# SCH_Argon_flow_controller_2021-09-11.net
KiCad netlist of a schematic drawn in EasyEDA
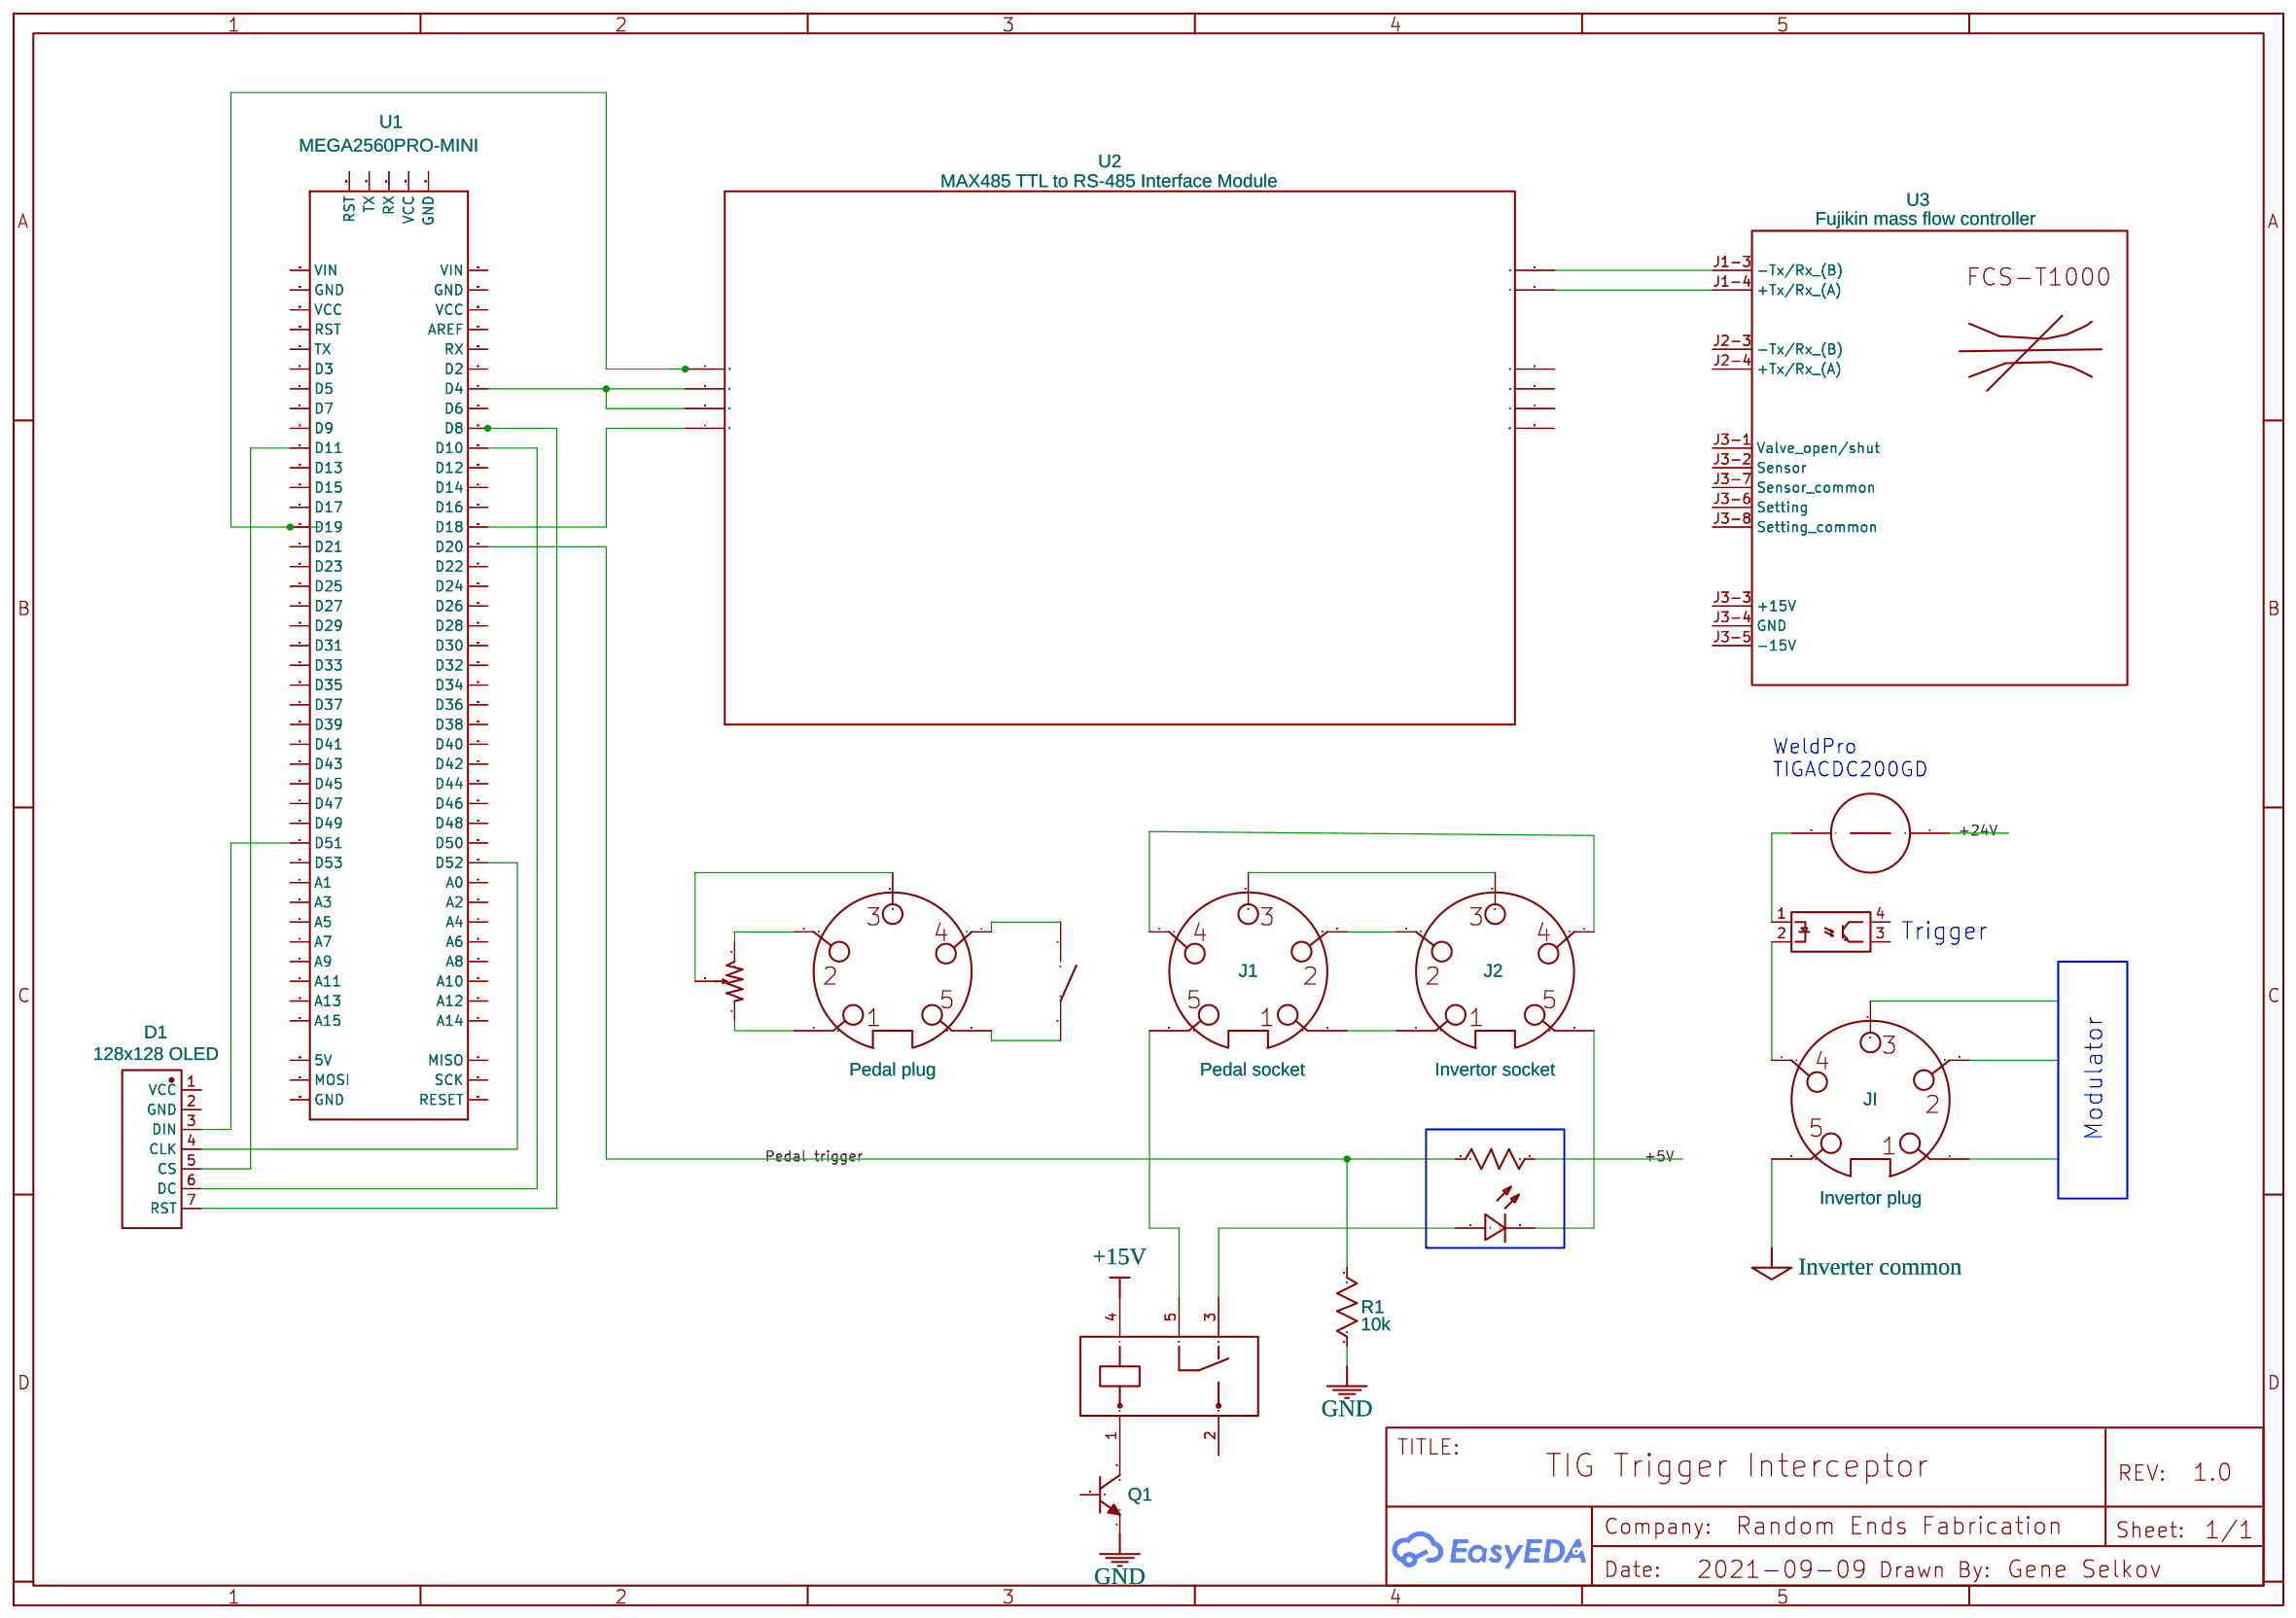
[diagram p0: schematic sheet]

(export (version "E")
  (design (tool "Eeschema 10.0.6"))
  (components
    (comp (ref "CS") (value "Current source") (libsource (lib "") (part "Current source")))
    (comp (ref "D1") (value "128x128 OLED") (libsource (lib "") (part "128x128 OLED")))
    (comp (ref "IC1")
      (value "Trigger")
      (libsource (lib "") (part "Optocoupler_SMD_KPC357_LTV35x_PC357_SingleChannel"))
    )
    (comp (ref "J0")
      (value "Pedal plug")
      (fields
        (field (name "BOM_Manufacturer Part") "Unknown")
        (field (name "BOM_Supplier Part") "CON-HK1705")
      )
      (libsource (lib "") (part "Weipu 5 connector_1"))
    )
    (comp (ref "J1")
      (value "Pedal socket")
      (fields
        (field (name "BOM_Manufacturer Part") "Unknown")
        (field (name "BOM_Supplier Part") "CON-HK1705")
      )
      (libsource (lib "") (part "Weipu 5 connector_3"))
    )
    (comp (ref "J2")
      (value "Invertor socket")
      (fields
        (field (name "BOM_Manufacturer Part") "Unknown")
        (field (name "BOM_Supplier Part") "CON-HK1705")
      )
      (libsource (lib "") (part "Weipu 5 connector_2"))
    )
    (comp (ref "JI")
      (value "Invertor plug")
      (fields
        (field (name "BOM_Manufacturer Part") "Unknown")
        (field (name "BOM_Supplier Part") "CON-HK1705")
      )
      (libsource (lib "") (part "Weipu 5 connector"))
    )
    (comp (ref "LED1")
      (value "LED-Red(0805)")
      (fields
        (field (name "BOM_Manufacturer Part") "17-21SURC/S530-A2/TR8")
        (field (name "BOM_Supplier Part") "C131244")
      )
      (libsource (lib "") (part "LED-Red(0805)"))
    )
    (comp (ref "PHR") (value "1 .. 40k") (libsource (lib "") (part "R_0603_US_1")))
    (comp (ref "POT") (value "POTENTIOMETER") (libsource (lib "") (part "POTENTIOMETER")))
    (comp (ref "Q1")
      (value "MPSA06-AT/P")
      (fields (field (name "BOM_Supplier Part") "C112894"))
      (libsource (lib "") (part "MPSA06-AT/P"))
    )
    (comp (ref "R1") (value "10k") (libsource (lib "") (part "R_0603_US")))
    (comp (ref "RELAY1")
      (value "SRD-12VDC-SL-C")
      (fields (field (name "BOM_Supplier Part") "C30431"))
      (libsource (lib "") (part "SRD-12VDC-SL-C"))
    )
    (comp (ref "S1") (value "Switch") (libsource (lib "") (part "Switch")))
    (comp (ref "U1") (value "MEGA2560PRO-MINI") (libsource (lib "") (part "MEGA2560PRO-MINI")))
    (comp (ref "U2")
      (value "MAX485 TTL to RS-485 Interface Module")
      (libsource (lib "") (part "MAX485 TTL to RS-485 Interface Module"))
    )
    (comp (ref "U3")
      (value "Fujikin mass flow controller")
      (fields (field (name "BOM_Manufacturer Part") "FCS-T1000"))
      (libsource (lib "") (part "Fujikin mass flow controller"))
    )
  )
  (nets
    (net (code "1") (name "+15V") (class "Default")
      (node (ref "RELAY1") (pin "4") (pinfunction "4_4") (pintype "input"))
    )
    (net (code "2") (name "/+5V") (class "Default")
      (node (ref "PHR") (pin "2") (pinfunction "2_2") (pintype "unspecified"))
    )
    (net (code "3") (name "/+24V") (class "Default")
      (node (ref "CS") (pin "1") (pinfunction "+_1") (pintype "unspecified"))
    )
    (net (code "4") (name "/Pedal trigger") (class "Default")
      (node (ref "PHR") (pin "1") (pinfunction "1_1") (pintype "unspecified"))
      (node (ref "R1") (pin "1") (pinfunction "1_1") (pintype "unspecified"))
      (node (ref "U1") (pin "D20") (pinfunction "D20_D20") (pintype "bidirectional"))
    )
    (net (code "5") (name "GND") (class "Default")
      (node (ref "Q1") (pin "1") (pinfunction "E_1") (pintype "input"))
      (node (ref "R1") (pin "2") (pinfunction "2_2") (pintype "unspecified"))
    )
    (net (code "6") (name "Inverter common") (class "Default")
      (node (ref "JI") (pin "5") (pinfunction "5_5") (pintype "unspecified"))
    )
    (net (code "7") (name "Net-(CS--)") (class "Default")
      (node (ref "CS") (pin "2") (pinfunction "-_2") (pintype "unspecified"))
      (node (ref "IC1") (pin "1") (pintype "unspecified"))
    )
    (net (code "8") (name "Net-(D1-CLK)") (class "Default")
      (node (ref "D1") (pin "4") (pinfunction "CLK_4") (pintype "input"))
      (node (ref "U1") (pin "D52") (pinfunction "D52_D52") (pintype "bidirectional"))
    )
    (net (code "9") (name "Net-(D1-CS)") (class "Default")
      (node (ref "D1") (pin "5") (pinfunction "CS_5") (pintype "input"))
      (node (ref "U1") (pin "D11") (pinfunction "D11_D11") (pintype "bidirectional"))
    )
    (net (code "10") (name "Net-(D1-DC)") (class "Default")
      (node (ref "D1") (pin "6") (pinfunction "DC_6") (pintype "unspecified"))
      (node (ref "U1") (pin "D10") (pinfunction "D10_D10") (pintype "bidirectional"))
    )
    (net (code "11") (name "Net-(D1-DIN)") (class "Default")
      (node (ref "D1") (pin "3") (pinfunction "DIN_3") (pintype "unspecified"))
      (node (ref "U1") (pin "D51") (pinfunction "D51_D51") (pintype "bidirectional"))
    )
    (net (code "12") (name "Net-(D1-RST)") (class "Default")
      (node (ref "D1") (pin "7") (pinfunction "RST_7") (pintype "input"))
      (node (ref "U1") (pin "D8") (pinfunction "D8_D8") (pintype "bidirectional"))
    )
    (net (code "13") (name "Net-(IC1-Pad2)") (class "Default")
      (node (ref "IC1") (pin "2") (pintype "unspecified"))
      (node (ref "JI") (pin "4") (pinfunction "4_4") (pintype "unspecified"))
    )
    (net (code "14") (name "Net-(J0-Pad1)") (class "Default")
      (node (ref "J0") (pin "1") (pinfunction "1_1") (pintype "unspecified"))
      (node (ref "POT") (pin "1") (pinfunction "1_1") (pintype "unspecified"))
    )
    (net (code "15") (name "Net-(J0-Pad2)") (class "Default")
      (node (ref "J0") (pin "2") (pinfunction "2_2") (pintype "unspecified"))
      (node (ref "POT") (pin "2") (pinfunction "2_2") (pintype "unspecified"))
    )
    (net (code "16") (name "Net-(J0-Pad3)") (class "Default")
      (node (ref "J0") (pin "3") (pinfunction "3_3") (pintype "unspecified"))
      (node (ref "POT") (pin "3") (pinfunction "3_3") (pintype "unspecified"))
    )
    (net (code "17") (name "Net-(J0-Pad4)") (class "Default")
      (node (ref "J0") (pin "4") (pinfunction "4_4") (pintype "unspecified"))
      (node (ref "S1") (pin "1") (pinfunction "1_1") (pintype "unspecified"))
    )
    (net (code "18") (name "Net-(J0-Pad5)") (class "Default")
      (node (ref "J0") (pin "5") (pinfunction "5_5") (pintype "unspecified"))
      (node (ref "S1") (pin "2") (pinfunction "2_2") (pintype "unspecified"))
    )
    (net (code "19") (name "Net-(J1-Pad1)") (class "Default")
      (node (ref "J1") (pin "1") (pinfunction "1_1") (pintype "unspecified"))
      (node (ref "J2") (pin "1") (pinfunction "1_1") (pintype "unspecified"))
    )
    (net (code "20") (name "Net-(J1-Pad2)") (class "Default")
      (node (ref "J1") (pin "2") (pinfunction "2_2") (pintype "unspecified"))
      (node (ref "J2") (pin "2") (pinfunction "2_2") (pintype "unspecified"))
    )
    (net (code "21") (name "Net-(J1-Pad3)") (class "Default")
      (node (ref "J1") (pin "3") (pinfunction "3_3") (pintype "unspecified"))
      (node (ref "J2") (pin "3") (pinfunction "3_3") (pintype "unspecified"))
    )
    (net (code "22") (name "Net-(J1-Pad4)") (class "Default")
      (node (ref "J1") (pin "4") (pinfunction "4_4") (pintype "unspecified"))
      (node (ref "J2") (pin "4") (pinfunction "4_4") (pintype "unspecified"))
    )
    (net (code "23") (name "Net-(J1-Pad5)") (class "Default")
      (node (ref "J1") (pin "5") (pinfunction "5_5") (pintype "unspecified"))
      (node (ref "RELAY1") (pin "5") (pinfunction "5_5") (pintype "input"))
    )
    (net (code "24") (name "Net-(LED1-+)") (class "Default")
      (node (ref "LED1") (pin "1") (pinfunction "+_1") (pintype "unspecified"))
      (node (ref "RELAY1") (pin "3") (pinfunction "3_3") (pintype "input"))
    )
    (net (code "25") (name "Net-(LED1--)") (class "Default")
      (node (ref "J2") (pin "5") (pinfunction "5_5") (pintype "unspecified"))
      (node (ref "LED1") (pin "2") (pinfunction "-_2") (pintype "unspecified"))
    )
    (net (code "26") (name "Net-(Q1-C)") (class "Default")
      (node (ref "Q1") (pin "3") (pinfunction "C_3") (pintype "input"))
      (node (ref "RELAY1") (pin "1") (pinfunction "1_1") (pintype "input"))
    )
    (net (code "27") (name "Net-(U2-A-Pad10)") (class "Default")
      (node (ref "U2") (pin "10") (pinfunction "A_10") (pintype "bidirectional"))
      (node (ref "U3") (pin "J1-4") (pinfunction "+Tx/Rx_(A)_J1-4") (pintype "bidirectional"))
    )
    (net (code "28") (name "Net-(U2-B-Pad9)") (class "Default")
      (node (ref "U2") (pin "9") (pinfunction "B_9") (pintype "bidirectional"))
      (node (ref "U3") (pin "J1-3") (pinfunction "-Tx/Rx_(B)_J1-3") (pintype "bidirectional"))
    )
    (net (code "29") (name "Net-(U2-DE)") (class "Default")
      (node (ref "U1") (pin "D4") (pinfunction "D4_D4") (pintype "bidirectional"))
      (node (ref "U2") (pin "2") (pinfunction "RE_2") (pintype "input"))
      (node (ref "U2") (pin "3") (pinfunction "DE_3") (pintype "input"))
    )
    (net (code "30") (name "Net-(U2-DI)") (class "Default")
      (node (ref "U1") (pin "D18") (pinfunction "D18_D18") (pintype "bidirectional"))
      (node (ref "U2") (pin "4") (pinfunction "DI_4") (pintype "input"))
    )
    (net (code "31") (name "Net-(U2-RO)") (class "Default")
      (node (ref "U1") (pin "D19") (pinfunction "D19_D19") (pintype "bidirectional"))
      (node (ref "U2") (pin "1") (pinfunction "RO_1") (pintype "output"))
    )
    (net (code "32") (name "unconnected-(D1-GND-Pad2)") (class "Default")
      (node (ref "D1") (pin "2") (pinfunction "GND_2") (pintype "passive"))
    )
    (net (code "33") (name "unconnected-(D1-VCC-Pad1)") (class "Default")
      (node (ref "D1") (pin "1") (pinfunction "VCC_1") (pintype "passive"))
    )
    (net (code "34") (name "unconnected-(IC1-Pad3)") (class "Default")
      (node (ref "IC1") (pin "3") (pintype "unspecified"))
    )
    (net (code "35") (name "unconnected-(IC1-Pad4)") (class "Default")
      (node (ref "IC1") (pin "4") (pintype "unspecified"))
    )
    (net (code "36") (name "unconnected-(JI-Pad1)") (class "Default")
      (node (ref "JI") (pin "1") (pinfunction "1_1") (pintype "unspecified"))
    )
    (net (code "37") (name "unconnected-(JI-Pad2)") (class "Default")
      (node (ref "JI") (pin "2") (pinfunction "2_2") (pintype "unspecified"))
    )
    (net (code "38") (name "unconnected-(JI-Pad3)") (class "Default")
      (node (ref "JI") (pin "3") (pinfunction "3_3") (pintype "unspecified"))
    )
    (net (code "39") (name "unconnected-(Q1-B-Pad2)") (class "Default")
      (node (ref "Q1") (pin "2") (pinfunction "B_2") (pintype "input"))
    )
    (net (code "40") (name "unconnected-(RELAY1-Pad2)") (class "Default")
      (node (ref "RELAY1") (pin "2") (pinfunction "2_2") (pintype "input"))
    )
    (net (code "41") (name "unconnected-(U1-5V-Pad5V@3)") (class "Default")
      (node (ref "U1") (pin "5V@3") (pinfunction "5V_5V@3") (pintype "bidirectional"))
    )
    (net (code "42") (name "unconnected-(U1-GND-PadGND@1)") (class "Default")
      (node (ref "U1") (pin "GND@1") (pinfunction "GND_GND@1") (pintype "bidirectional"))
    )
    (net (code "43") (name "unconnected-(U1-GND-PadGND@2)") (class "Default")
      (node (ref "U1") (pin "GND@2") (pinfunction "GND_GND@2") (pintype "bidirectional"))
    )
    (net (code "44") (name "unconnected-(U1-GND-PadGND@3)") (class "Default")
      (node (ref "U1") (pin "GND@3") (pinfunction "GND_GND@3") (pintype "bidirectional"))
    )
    (net (code "45") (name "unconnected-(U1-GND-PadGND@4)") (class "Default")
      (node (ref "U1") (pin "GND@4") (pinfunction "GND_GND@4") (pintype "bidirectional"))
    )
    (net (code "46") (name "unconnected-(U1-PadA0)") (class "Default")
      (node (ref "U1") (pin "A0") (pinfunction "A0_A0") (pintype "bidirectional"))
    )
    (net (code "47") (name "unconnected-(U1-PadA1)") (class "Default")
      (node (ref "U1") (pin "A1") (pinfunction "A1_A1") (pintype "bidirectional"))
    )
    (net (code "48") (name "unconnected-(U1-PadA2)") (class "Default")
      (node (ref "U1") (pin "A2") (pinfunction "A2_A2") (pintype "bidirectional"))
    )
    (net (code "49") (name "unconnected-(U1-PadA3)") (class "Default")
      (node (ref "U1") (pin "A3") (pinfunction "A3_A3") (pintype "bidirectional"))
    )
    (net (code "50") (name "unconnected-(U1-PadA4)") (class "Default")
      (node (ref "U1") (pin "A4") (pinfunction "A4_A4") (pintype "bidirectional"))
    )
    (net (code "51") (name "unconnected-(U1-PadA5)") (class "Default")
      (node (ref "U1") (pin "A5") (pinfunction "A5_A5") (pintype "bidirectional"))
    )
    (net (code "52") (name "unconnected-(U1-PadA6)") (class "Default")
      (node (ref "U1") (pin "A6") (pinfunction "A6_A6") (pintype "bidirectional"))
    )
    (net (code "53") (name "unconnected-(U1-PadA7)") (class "Default")
      (node (ref "U1") (pin "A7") (pinfunction "A7_A7") (pintype "bidirectional"))
    )
    (net (code "54") (name "unconnected-(U1-PadA8)") (class "Default")
      (node (ref "U1") (pin "A8") (pinfunction "A8_A8") (pintype "bidirectional"))
    )
    (net (code "55") (name "unconnected-(U1-PadA9)") (class "Default")
      (node (ref "U1") (pin "A9") (pinfunction "A9_A9") (pintype "bidirectional"))
    )
    (net (code "56") (name "unconnected-(U1-PadA10)") (class "Default")
      (node (ref "U1") (pin "A10") (pinfunction "A10_A10") (pintype "bidirectional"))
    )
    (net (code "57") (name "unconnected-(U1-PadA11)") (class "Default")
      (node (ref "U1") (pin "A11") (pinfunction "A11_A11") (pintype "bidirectional"))
    )
    (net (code "58") (name "unconnected-(U1-PadA12)") (class "Default")
      (node (ref "U1") (pin "A12") (pinfunction "A12_A12") (pintype "bidirectional"))
    )
    (net (code "59") (name "unconnected-(U1-PadA13)") (class "Default")
      (node (ref "U1") (pin "A13") (pinfunction "A13_A13") (pintype "bidirectional"))
    )
    (net (code "60") (name "unconnected-(U1-PadA14)") (class "Default")
      (node (ref "U1") (pin "A14") (pinfunction "A14_A14") (pintype "bidirectional"))
    )
    (net (code "61") (name "unconnected-(U1-PadA15)") (class "Default")
      (node (ref "U1") (pin "A15") (pinfunction "A15_A15") (pintype "bidirectional"))
    )
    (net (code "62") (name "unconnected-(U1-PadAREF)") (class "Default")
      (node (ref "U1") (pin "AREF") (pinfunction "AREF_AREF") (pintype "bidirectional"))
    )
    (net (code "63") (name "unconnected-(U1-PadD2)") (class "Default")
      (node (ref "U1") (pin "D2") (pinfunction "D2_D2") (pintype "bidirectional"))
    )
    (net (code "64") (name "unconnected-(U1-PadD3)") (class "Default")
      (node (ref "U1") (pin "D3") (pinfunction "D3_D3") (pintype "bidirectional"))
    )
    (net (code "65") (name "unconnected-(U1-PadD5)") (class "Default")
      (node (ref "U1") (pin "D5") (pinfunction "D5_D5") (pintype "bidirectional"))
    )
    (net (code "66") (name "unconnected-(U1-PadD6)") (class "Default")
      (node (ref "U1") (pin "D6") (pinfunction "D6_D6") (pintype "bidirectional"))
    )
    (net (code "67") (name "unconnected-(U1-PadD7)") (class "Default")
      (node (ref "U1") (pin "D7") (pinfunction "D7_D7") (pintype "bidirectional"))
    )
    (net (code "68") (name "unconnected-(U1-PadD9)") (class "Default")
      (node (ref "U1") (pin "D9") (pinfunction "D9_D9") (pintype "bidirectional"))
    )
    (net (code "69") (name "unconnected-(U1-PadD12)") (class "Default")
      (node (ref "U1") (pin "D12") (pinfunction "D12_D12") (pintype "bidirectional"))
    )
    (net (code "70") (name "unconnected-(U1-PadD13)") (class "Default")
      (node (ref "U1") (pin "D13") (pinfunction "D13_D13") (pintype "bidirectional"))
    )
    (net (code "71") (name "unconnected-(U1-PadD14)") (class "Default")
      (node (ref "U1") (pin "D14") (pinfunction "D14_D14") (pintype "bidirectional"))
    )
    (net (code "72") (name "unconnected-(U1-PadD15)") (class "Default")
      (node (ref "U1") (pin "D15") (pinfunction "D15_D15") (pintype "bidirectional"))
    )
    (net (code "73") (name "unconnected-(U1-PadD16)") (class "Default")
      (node (ref "U1") (pin "D16") (pinfunction "D16_D16") (pintype "bidirectional"))
    )
    (net (code "74") (name "unconnected-(U1-PadD17)") (class "Default")
      (node (ref "U1") (pin "D17") (pinfunction "D17_D17") (pintype "bidirectional"))
    )
    (net (code "75") (name "unconnected-(U1-PadD21)") (class "Default")
      (node (ref "U1") (pin "D21") (pinfunction "D21_D21") (pintype "bidirectional"))
    )
    (net (code "76") (name "unconnected-(U1-PadD22)") (class "Default")
      (node (ref "U1") (pin "D22") (pinfunction "D22_D22") (pintype "bidirectional"))
    )
    (net (code "77") (name "unconnected-(U1-PadD23)") (class "Default")
      (node (ref "U1") (pin "D23") (pinfunction "D23_D23") (pintype "bidirectional"))
    )
    (net (code "78") (name "unconnected-(U1-PadD24)") (class "Default")
      (node (ref "U1") (pin "D24") (pinfunction "D24_D24") (pintype "bidirectional"))
    )
    (net (code "79") (name "unconnected-(U1-PadD25)") (class "Default")
      (node (ref "U1") (pin "D25") (pinfunction "D25_D25") (pintype "bidirectional"))
    )
    (net (code "80") (name "unconnected-(U1-PadD26)") (class "Default")
      (node (ref "U1") (pin "D26") (pinfunction "D26_D26") (pintype "bidirectional"))
    )
    (net (code "81") (name "unconnected-(U1-PadD27)") (class "Default")
      (node (ref "U1") (pin "D27") (pinfunction "D27_D27") (pintype "bidirectional"))
    )
    (net (code "82") (name "unconnected-(U1-PadD28)") (class "Default")
      (node (ref "U1") (pin "D28") (pinfunction "D28_D28") (pintype "bidirectional"))
    )
    (net (code "83") (name "unconnected-(U1-PadD29)") (class "Default")
      (node (ref "U1") (pin "D29") (pinfunction "D29_D29") (pintype "bidirectional"))
    )
    (net (code "84") (name "unconnected-(U1-PadD30)") (class "Default")
      (node (ref "U1") (pin "D30") (pinfunction "D30_D30") (pintype "bidirectional"))
    )
    (net (code "85") (name "unconnected-(U1-PadD31)") (class "Default")
      (node (ref "U1") (pin "D31") (pinfunction "D31_D31") (pintype "bidirectional"))
    )
    (net (code "86") (name "unconnected-(U1-PadD32)") (class "Default")
      (node (ref "U1") (pin "D32") (pinfunction "D32_D32") (pintype "bidirectional"))
    )
    (net (code "87") (name "unconnected-(U1-PadD33)") (class "Default")
      (node (ref "U1") (pin "D33") (pinfunction "D33_D33") (pintype "bidirectional"))
    )
    (net (code "88") (name "unconnected-(U1-PadD34)") (class "Default")
      (node (ref "U1") (pin "D34") (pinfunction "D34_D34") (pintype "bidirectional"))
    )
    (net (code "89") (name "unconnected-(U1-PadD35)") (class "Default")
      (node (ref "U1") (pin "D35") (pinfunction "D35_D35") (pintype "bidirectional"))
    )
    (net (code "90") (name "unconnected-(U1-PadD36)") (class "Default")
      (node (ref "U1") (pin "D36") (pinfunction "D36_D36") (pintype "bidirectional"))
    )
    (net (code "91") (name "unconnected-(U1-PadD37)") (class "Default")
      (node (ref "U1") (pin "D37") (pinfunction "D37_D37") (pintype "bidirectional"))
    )
    (net (code "92") (name "unconnected-(U1-PadD38)") (class "Default")
      (node (ref "U1") (pin "D38") (pinfunction "D38_D38") (pintype "bidirectional"))
    )
    (net (code "93") (name "unconnected-(U1-PadD39)") (class "Default")
      (node (ref "U1") (pin "D39") (pinfunction "D39_D39") (pintype "bidirectional"))
    )
    (net (code "94") (name "unconnected-(U1-PadD40)") (class "Default")
      (node (ref "U1") (pin "D40") (pinfunction "D40_D40") (pintype "bidirectional"))
    )
    (net (code "95") (name "unconnected-(U1-PadD41)") (class "Default")
      (node (ref "U1") (pin "D41") (pinfunction "D41_D41") (pintype "bidirectional"))
    )
    (net (code "96") (name "unconnected-(U1-PadD42)") (class "Default")
      (node (ref "U1") (pin "D42") (pinfunction "D42_D42") (pintype "bidirectional"))
    )
    (net (code "97") (name "unconnected-(U1-PadD43)") (class "Default")
      (node (ref "U1") (pin "D43") (pinfunction "D43_D43") (pintype "bidirectional"))
    )
    (net (code "98") (name "unconnected-(U1-PadD44)") (class "Default")
      (node (ref "U1") (pin "D44") (pinfunction "D44_D44") (pintype "bidirectional"))
    )
    (net (code "99") (name "unconnected-(U1-PadD45)") (class "Default")
      (node (ref "U1") (pin "D45") (pinfunction "D45_D45") (pintype "bidirectional"))
    )
    (net (code "100") (name "unconnected-(U1-PadD46)") (class "Default")
      (node (ref "U1") (pin "D46") (pinfunction "D46_D46") (pintype "bidirectional"))
    )
    (net (code "101") (name "unconnected-(U1-PadD47)") (class "Default")
      (node (ref "U1") (pin "D47") (pinfunction "D47_D47") (pintype "bidirectional"))
    )
    (net (code "102") (name "unconnected-(U1-PadD48)") (class "Default")
      (node (ref "U1") (pin "D48") (pinfunction "D48_D48") (pintype "bidirectional"))
    )
    (net (code "103") (name "unconnected-(U1-PadD49)") (class "Default")
      (node (ref "U1") (pin "D49") (pinfunction "D49_D49") (pintype "bidirectional"))
    )
    (net (code "104") (name "unconnected-(U1-PadD50)") (class "Default")
      (node (ref "U1") (pin "D50") (pinfunction "D50_D50") (pintype "bidirectional"))
    )
    (net (code "105") (name "unconnected-(U1-PadD53)") (class "Default")
      (node (ref "U1") (pin "D53") (pinfunction "D53_D53") (pintype "bidirectional"))
    )
    (net (code "106") (name "unconnected-(U1-PadMISO)") (class "Default")
      (node (ref "U1") (pin "MISO") (pinfunction "MISO_MISO") (pintype "bidirectional"))
    )
    (net (code "107") (name "unconnected-(U1-PadMOSI)") (class "Default")
      (node (ref "U1") (pin "MOSI") (pinfunction "MOSI_MOSI") (pintype "bidirectional"))
    )
    (net (code "108") (name "unconnected-(U1-PadRESET)") (class "Default")
      (node (ref "U1") (pin "RESET") (pinfunction "RESET_RESET") (pintype "bidirectional"))
    )
    (net (code "109") (name "unconnected-(U1-PadSCK)") (class "Default")
      (node (ref "U1") (pin "SCK") (pinfunction "SCK_SCK") (pintype "bidirectional"))
    )
    (net (code "110") (name "unconnected-(U1-RST-PadRST@1)") (class "Default")
      (node (ref "U1") (pin "RST@1") (pinfunction "RST_RST@1") (pintype "bidirectional"))
    )
    (net (code "111") (name "unconnected-(U1-RST-PadRST@2)") (class "Default")
      (node (ref "U1") (pin "RST@2") (pinfunction "RST_RST@2") (pintype "bidirectional"))
    )
    (net (code "112") (name "unconnected-(U1-RX-PadRX@1)") (class "Default")
      (node (ref "U1") (pin "RX@1") (pinfunction "RX_RX@1") (pintype "bidirectional"))
    )
    (net (code "113") (name "unconnected-(U1-RX-PadRX@2)") (class "Default")
      (node (ref "U1") (pin "RX@2") (pinfunction "RX_RX@2") (pintype "bidirectional"))
    )
    (net (code "114") (name "unconnected-(U1-TX-PadTX@1)") (class "Default")
      (node (ref "U1") (pin "TX@1") (pinfunction "TX_TX@1") (pintype "bidirectional"))
    )
    (net (code "115") (name "unconnected-(U1-TX-PadTX@2)") (class "Default")
      (node (ref "U1") (pin "TX@2") (pinfunction "TX_TX@2") (pintype "bidirectional"))
    )
    (net (code "116") (name "unconnected-(U1-VCC-PadVCC@1)") (class "Default")
      (node (ref "U1") (pin "VCC@1") (pinfunction "VCC_VCC@1") (pintype "bidirectional"))
    )
    (net (code "117") (name "unconnected-(U1-VCC-PadVCC@2)") (class "Default")
      (node (ref "U1") (pin "VCC@2") (pinfunction "VCC_VCC@2") (pintype "bidirectional"))
    )
    (net (code "118") (name "unconnected-(U1-VCC-PadVCC@3)") (class "Default")
      (node (ref "U1") (pin "VCC@3") (pinfunction "VCC_VCC@3") (pintype "bidirectional"))
    )
    (net (code "119") (name "unconnected-(U1-VIN-PadVIN@1)") (class "Default")
      (node (ref "U1") (pin "VIN@1") (pinfunction "VIN_VIN@1") (pintype "bidirectional"))
    )
    (net (code "120") (name "unconnected-(U1-VIN-PadVIN@2)") (class "Default")
      (node (ref "U1") (pin "VIN@2") (pinfunction "VIN_VIN@2") (pintype "bidirectional"))
    )
    (net (code "121") (name "unconnected-(U2-5V-Pad5)") (class "Default")
      (node (ref "U2") (pin "5") (pinfunction "5V_5") (pintype "passive"))
    )
    (net (code "122") (name "unconnected-(U2-A-Pad7)") (class "Default")
      (node (ref "U2") (pin "7") (pinfunction "A_7") (pintype "bidirectional"))
    )
    (net (code "123") (name "unconnected-(U2-B-Pad6)") (class "Default")
      (node (ref "U2") (pin "6") (pinfunction "B_6") (pintype "bidirectional"))
    )
    (net (code "124") (name "unconnected-(U2-GND-Pad8)") (class "Default")
      (node (ref "U2") (pin "8") (pinfunction "GND_8") (pintype "passive"))
    )
    (net (code "125") (name "unconnected-(U3-+15V-PadJ3-3)") (class "Default")
      (node (ref "U3") (pin "J3-3") (pinfunction "+15V_J3-3") (pintype "passive"))
    )
    (net (code "126") (name "unconnected-(U3-+Tx{slash}Rx_(A)-PadJ2-4)") (class "Default")
      (node (ref "U3") (pin "J2-4") (pinfunction "+Tx/Rx_(A)_J2-4") (pintype "bidirectional"))
    )
    (net (code "127") (name "unconnected-(U3--15V-PadJ3-5)") (class "Default")
      (node (ref "U3") (pin "J3-5") (pinfunction "-15V_J3-5") (pintype "passive"))
    )
    (net (code "128") (name "unconnected-(U3--Tx{slash}Rx_(B)-PadJ2-3)") (class "Default")
      (node (ref "U3") (pin "J2-3") (pinfunction "-Tx/Rx_(B)_J2-3") (pintype "bidirectional"))
    )
    (net (code "129") (name "unconnected-(U3-GND-PadJ3-4)") (class "Default")
      (node (ref "U3") (pin "J3-4") (pinfunction "GND_J3-4") (pintype "passive"))
    )
    (net (code "130") (name "unconnected-(U3-Sensor-PadJ3-2)") (class "Default")
      (node (ref "U3") (pin "J3-2") (pinfunction "Sensor_J3-2") (pintype "output"))
    )
    (net (code "131") (name "unconnected-(U3-Sensor_common-PadJ3-7)") (class "Default")
      (node (ref "U3") (pin "J3-7") (pinfunction "Sensor_common_J3-7") (pintype "output"))
    )
    (net (code "132") (name "unconnected-(U3-Setting-PadJ3-6)") (class "Default")
      (node (ref "U3") (pin "J3-6") (pinfunction "Setting_J3-6") (pintype "input"))
    )
    (net (code "133") (name "unconnected-(U3-Setting_common-PadJ3-8)") (class "Default")
      (node (ref "U3") (pin "J3-8") (pinfunction "Setting_common_J3-8") (pintype "input"))
    )
    (net (code "134") (name "unconnected-(U3-Valve_open{slash}shut-PadJ3-1)") (class "Default")
      (node (ref "U3") (pin "J3-1") (pinfunction "Valve_open/shut_J3-1") (pintype "unspecified"))
    )
  )
)
